# TXn_v1_2_bottomonly.net
KiCad netlist of a schematic drawn in EAGLE
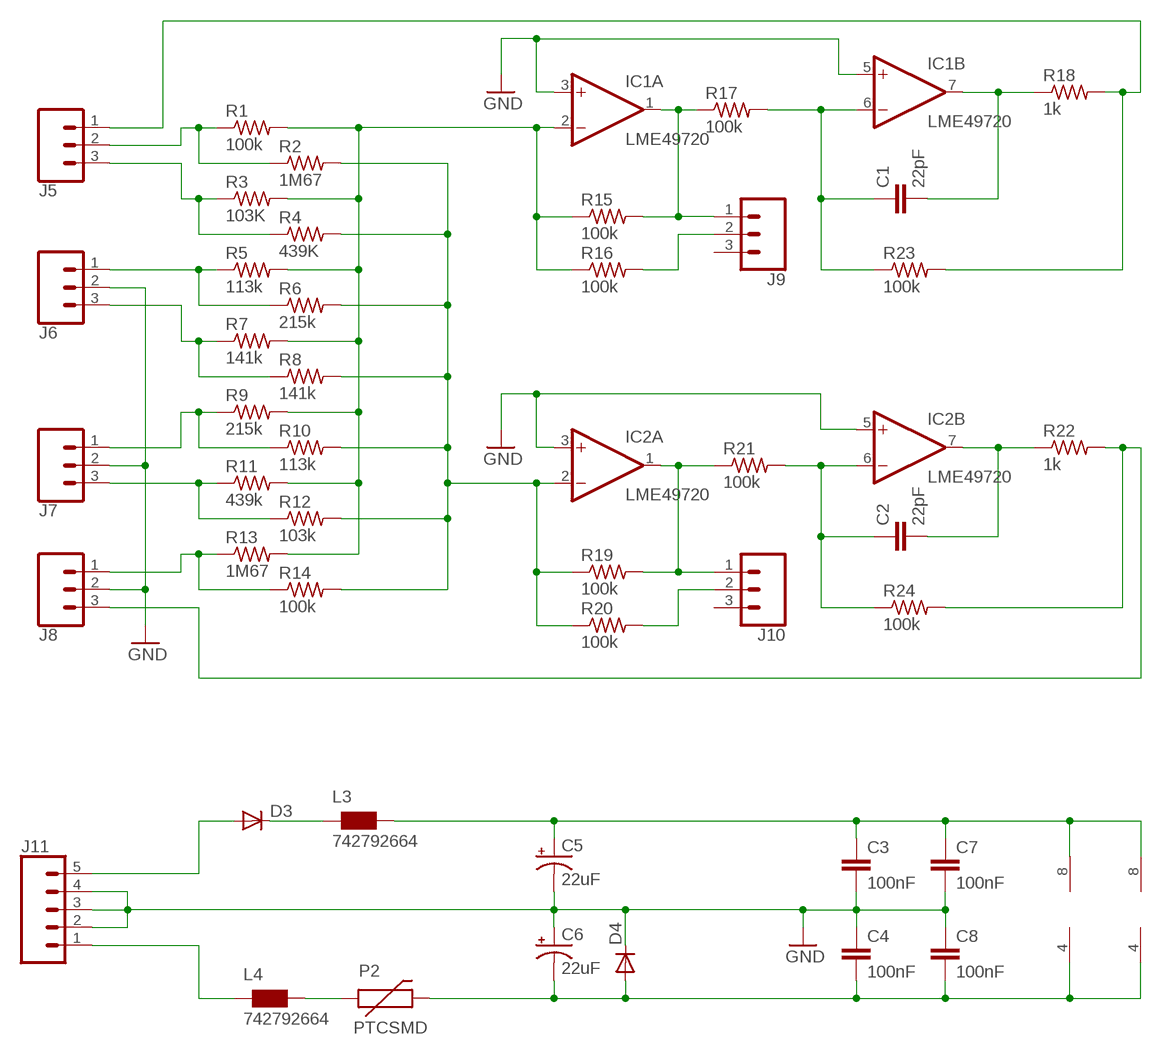
[diagram p0: schematic, sheet 1]

(export (version "E")
  (design (tool "Eeschema 10.0.6"))
  (components
    (comp (ref "C1")
      (value "22pF")
      (footprint "eagle-import:0603-CAP")
      (libsource (lib "eagle-import") (part "CAP0603-CAP"))
    )
    (comp (ref "C2")
      (value "22pF")
      (footprint "eagle-import:0603-CAP")
      (libsource (lib "eagle-import") (part "CAP0603-CAP"))
    )
    (comp (ref "C3")
      (value "100nF")
      (footprint "eagle-import:0603-CAP")
      (libsource (lib "eagle-import") (part "CAP0603-CAP"))
    )
    (comp (ref "C4")
      (value "100nF")
      (footprint "eagle-import:0603-CAP")
      (libsource (lib "eagle-import") (part "CAP0603-CAP"))
    )
    (comp (ref "C5")
      (value "22uF")
      (footprint "eagle-import:PANASONIC_B")
      (libsource (lib "eagle-import") (part "CPOL-USB"))
    )
    (comp (ref "C6")
      (value "22uF")
      (footprint "eagle-import:PANASONIC_B")
      (libsource (lib "eagle-import") (part "CPOL-USB"))
    )
    (comp (ref "C7")
      (value "100nF")
      (footprint "eagle-import:0603-CAP")
      (libsource (lib "eagle-import") (part "CAP0603-CAP"))
    )
    (comp (ref "C8")
      (value "100nF")
      (footprint "eagle-import:0603-CAP")
      (libsource (lib "eagle-import") (part "CAP0603-CAP"))
    )
    (comp (ref "D3")
      (value "DIODE-SOD123")
      (footprint "eagle-import:SOD123")
      (libsource (lib "eagle-import") (part "DIODE-SOD123"))
    )
    (comp (ref "D4")
      (value "DIODE-SOD123")
      (footprint "eagle-import:SOD123")
      (libsource (lib "eagle-import") (part "DIODE-SOD123"))
    )
    (comp (ref "IC1")
      (value "LME49720")
      (footprint "eagle-import:SO08")
      (fields (field (name "SPICEPREFIX") "J"))
      (libsource (lib "eagle-import") (part "TL072D"))
    )
    (comp (ref "IC2")
      (value "LME49720")
      (footprint "eagle-import:SO08")
      (libsource (lib "eagle-import") (part "TL072D"))
    )
    (comp (ref "J5")
      (value "CONN_031X03_NO_SILK")
      (footprint "eagle-import:1X03_NO_SILK")
      (libsource (lib "eagle-import") (part "CONN_031X03_NO_SILK"))
    )
    (comp (ref "J6")
      (value "CONN_031X03_NO_SILK")
      (footprint "eagle-import:1X03_NO_SILK")
      (libsource (lib "eagle-import") (part "CONN_031X03_NO_SILK"))
    )
    (comp (ref "J7")
      (value "CONN_031X03_NO_SILK")
      (footprint "eagle-import:1X03_NO_SILK")
      (libsource (lib "eagle-import") (part "CONN_031X03_NO_SILK"))
    )
    (comp (ref "J8")
      (value "CONN_031X03_NO_SILK")
      (footprint "eagle-import:1X03_NO_SILK")
      (libsource (lib "eagle-import") (part "CONN_031X03_NO_SILK"))
    )
    (comp (ref "J9")
      (value "CONN_031X03_NO_SILK")
      (footprint "eagle-import:1X03_NO_SILK")
      (libsource (lib "eagle-import") (part "CONN_031X03_NO_SILK"))
    )
    (comp (ref "J10")
      (value "CONN_031X03_NO_SILK")
      (footprint "eagle-import:1X03_NO_SILK")
      (libsource (lib "eagle-import") (part "CONN_031X03_NO_SILK"))
    )
    (comp (ref "J11")
      (value "CONN_05NO_SILK")
      (footprint "eagle-import:1X05_NO_SILK")
      (libsource (lib "eagle-import") (part "CONN_05NO_SILK"))
    )
    (comp (ref "L3")
      (value "742792664")
      (footprint "eagle-import:0603")
      (libsource (lib "eagle-import") (part "WE-CBF_0603"))
    )
    (comp (ref "L4")
      (value "742792664")
      (footprint "eagle-import:0603")
      (libsource (lib "eagle-import") (part "WE-CBF_0603"))
    )
    (comp (ref "P2")
      (value "PTCSMD")
      (footprint "eagle-import:PTC-1206")
      (libsource (lib "eagle-import") (part "PTCSMD"))
    )
    (comp (ref "R1")
      (value "100k")
      (footprint "eagle-import:R0603")
      (libsource (lib "eagle-import") (part "R-US_R0603"))
    )
    (comp (ref "R2")
      (value "1M67")
      (footprint "eagle-import:R0603")
      (libsource (lib "eagle-import") (part "R-US_R0603"))
    )
    (comp (ref "R3")
      (value "103K")
      (footprint "eagle-import:R0603")
      (libsource (lib "eagle-import") (part "R-US_R0603"))
    )
    (comp (ref "R4")
      (value "439K")
      (footprint "eagle-import:R0603")
      (libsource (lib "eagle-import") (part "R-US_R0603"))
    )
    (comp (ref "R5")
      (value "113k")
      (footprint "eagle-import:R0603")
      (libsource (lib "eagle-import") (part "R-US_R0603"))
    )
    (comp (ref "R6")
      (value "215k")
      (footprint "eagle-import:R0603")
      (libsource (lib "eagle-import") (part "R-US_R0603"))
    )
    (comp (ref "R7")
      (value "141k")
      (footprint "eagle-import:R0603")
      (libsource (lib "eagle-import") (part "R-US_R0603"))
    )
    (comp (ref "R8")
      (value "141k")
      (footprint "eagle-import:R0603")
      (libsource (lib "eagle-import") (part "R-US_R0603"))
    )
    (comp (ref "R9")
      (value "215k")
      (footprint "eagle-import:R0603")
      (libsource (lib "eagle-import") (part "R-US_R0603"))
    )
    (comp (ref "R10")
      (value "113k")
      (footprint "eagle-import:R0603")
      (libsource (lib "eagle-import") (part "R-US_R0603"))
    )
    (comp (ref "R11")
      (value "439k")
      (footprint "eagle-import:R0603")
      (libsource (lib "eagle-import") (part "R-US_R0603"))
    )
    (comp (ref "R12")
      (value "103k")
      (footprint "eagle-import:R0603")
      (libsource (lib "eagle-import") (part "R-US_R0603"))
    )
    (comp (ref "R13")
      (value "1M67")
      (footprint "eagle-import:R0603")
      (libsource (lib "eagle-import") (part "R-US_R0603"))
    )
    (comp (ref "R14")
      (value "100k")
      (footprint "eagle-import:R0603")
      (libsource (lib "eagle-import") (part "R-US_R0603"))
    )
    (comp (ref "R15")
      (value "100k")
      (footprint "eagle-import:R0603")
      (libsource (lib "eagle-import") (part "R-US_R0603"))
    )
    (comp (ref "R16")
      (value "100k")
      (footprint "eagle-import:R0603")
      (libsource (lib "eagle-import") (part "R-US_R0603"))
    )
    (comp (ref "R17")
      (value "100k")
      (footprint "eagle-import:R0603")
      (libsource (lib "eagle-import") (part "R-US_R0603"))
    )
    (comp (ref "R18")
      (value "1k")
      (footprint "eagle-import:R0603")
      (libsource (lib "eagle-import") (part "R-US_R0603"))
    )
    (comp (ref "R19")
      (value "100k")
      (footprint "eagle-import:R0603")
      (libsource (lib "eagle-import") (part "R-US_R0603"))
    )
    (comp (ref "R20")
      (value "100k")
      (footprint "eagle-import:R0603")
      (libsource (lib "eagle-import") (part "R-US_R0603"))
    )
    (comp (ref "R21")
      (value "100k")
      (footprint "eagle-import:R0603")
      (libsource (lib "eagle-import") (part "R-US_R0603"))
    )
    (comp (ref "R22")
      (value "1k")
      (footprint "eagle-import:R0603")
      (libsource (lib "eagle-import") (part "R-US_R0603"))
    )
    (comp (ref "R23")
      (value "100k")
      (footprint "eagle-import:R0603")
      (libsource (lib "eagle-import") (part "R-US_R0603"))
    )
    (comp (ref "R24")
      (value "100k")
      (footprint "eagle-import:R0603")
      (libsource (lib "eagle-import") (part "R-US_R0603"))
    )
  )
  (nets
    (net (code "1") (name "GND") (class "Default")
      (node (ref "C3") (pin "2") (pinfunction "2_2") (pintype "passive"))
      (node (ref "C4") (pin "1") (pinfunction "1_1") (pintype "passive"))
      (node (ref "C5") (pin "-") (pinfunction "-_-") (pintype "passive"))
      (node (ref "C6") (pin "+") (pinfunction "+_+") (pintype "passive"))
      (node (ref "C7") (pin "2") (pinfunction "2_2") (pintype "passive"))
      (node (ref "C8") (pin "1") (pinfunction "1_1") (pintype "passive"))
      (node (ref "D4") (pin "C") (pinfunction "C_C") (pintype "passive"))
      (node (ref "IC1") (pin "3") (pinfunction "+IN_3") (pintype "input"))
      (node (ref "IC1") (pin "5") (pinfunction "+IN_5") (pintype "input"))
      (node (ref "IC2") (pin "3") (pinfunction "+IN_3") (pintype "input"))
      (node (ref "IC2") (pin "5") (pinfunction "+IN_5") (pintype "input"))
      (node (ref "J11") (pin "2") (pinfunction "2_2") (pintype "passive"))
      (node (ref "J11") (pin "3") (pinfunction "3_3") (pintype "passive"))
      (node (ref "J11") (pin "4") (pinfunction "4_4") (pintype "passive"))
      (node (ref "J6") (pin "2") (pinfunction "2_2") (pintype "passive"))
      (node (ref "J7") (pin "2") (pinfunction "2_2") (pintype "passive"))
      (node (ref "J8") (pin "2") (pinfunction "2_2") (pintype "passive"))
    )
    (net (code "2") (name "Net-(D3-PadA)") (class "Default")
      (node (ref "D3") (pin "A") (pinfunction "A_A") (pintype "passive"))
      (node (ref "J11") (pin "5") (pinfunction "5_5") (pintype "passive"))
    )
    (net (code "3") (name "Net-(D3-PadC)") (class "Default")
      (node (ref "D3") (pin "C") (pinfunction "C_C") (pintype "passive"))
      (node (ref "L3") (pin "1") (pinfunction "1_1") (pintype "passive"))
    )
    (net (code "4") (name "Net-(IC1A--IN)") (class "Default")
      (node (ref "IC1") (pin "2") (pinfunction "-IN_2") (pintype "input"))
      (node (ref "R1") (pin "2") (pinfunction "2_2") (pintype "passive"))
      (node (ref "R11") (pin "2") (pinfunction "2_2") (pintype "passive"))
      (node (ref "R13") (pin "2") (pinfunction "2_2") (pintype "passive"))
      (node (ref "R15") (pin "1") (pinfunction "1_1") (pintype "passive"))
      (node (ref "R16") (pin "1") (pinfunction "1_1") (pintype "passive"))
      (node (ref "R3") (pin "2") (pinfunction "2_2") (pintype "passive"))
      (node (ref "R5") (pin "2") (pinfunction "2_2") (pintype "passive"))
      (node (ref "R7") (pin "2") (pinfunction "2_2") (pintype "passive"))
      (node (ref "R9") (pin "2") (pinfunction "2_2") (pintype "passive"))
    )
    (net (code "5") (name "Net-(IC1A-OUT)") (class "Default")
      (node (ref "IC1") (pin "1") (pinfunction "OUT_1") (pintype "output"))
      (node (ref "J9") (pin "1") (pinfunction "1_1") (pintype "passive"))
      (node (ref "R15") (pin "2") (pinfunction "2_2") (pintype "passive"))
      (node (ref "R17") (pin "1") (pinfunction "1_1") (pintype "passive"))
    )
    (net (code "6") (name "Net-(IC1B--IN)") (class "Default")
      (node (ref "C1") (pin "1") (pinfunction "1_1") (pintype "passive"))
      (node (ref "IC1") (pin "6") (pinfunction "-IN_6") (pintype "input"))
      (node (ref "R17") (pin "2") (pinfunction "2_2") (pintype "passive"))
      (node (ref "R23") (pin "1") (pinfunction "1_1") (pintype "passive"))
    )
    (net (code "7") (name "Net-(IC1B-OUT)") (class "Default")
      (node (ref "C1") (pin "2") (pinfunction "2_2") (pintype "passive"))
      (node (ref "IC1") (pin "7") (pinfunction "OUT_7") (pintype "output"))
      (node (ref "R18") (pin "1") (pinfunction "1_1") (pintype "passive"))
    )
    (net (code "8") (name "Net-(IC1C-V+)") (class "Default")
      (node (ref "C3") (pin "1") (pinfunction "1_1") (pintype "passive"))
      (node (ref "C5") (pin "+") (pinfunction "+_+") (pintype "passive"))
      (node (ref "C7") (pin "1") (pinfunction "1_1") (pintype "passive"))
      (node (ref "IC1") (pin "8") (pinfunction "V+_8") (pintype "power_in"))
      (node (ref "IC2") (pin "8") (pinfunction "V+_8") (pintype "power_in"))
      (node (ref "L3") (pin "2") (pinfunction "2_2") (pintype "passive"))
    )
    (net (code "9") (name "Net-(IC1C-V-)") (class "Default")
      (node (ref "C4") (pin "2") (pinfunction "2_2") (pintype "passive"))
      (node (ref "C6") (pin "-") (pinfunction "-_-") (pintype "passive"))
      (node (ref "C8") (pin "2") (pinfunction "2_2") (pintype "passive"))
      (node (ref "D4") (pin "A") (pinfunction "A_A") (pintype "passive"))
      (node (ref "IC1") (pin "4") (pinfunction "V-_4") (pintype "power_in"))
      (node (ref "IC2") (pin "4") (pinfunction "V-_4") (pintype "power_in"))
      (node (ref "P2") (pin "2") (pinfunction "2_2") (pintype "bidirectional"))
    )
    (net (code "10") (name "Net-(IC2A--IN)") (class "Default")
      (node (ref "IC2") (pin "2") (pinfunction "-IN_2") (pintype "input"))
      (node (ref "R10") (pin "2") (pinfunction "2_2") (pintype "passive"))
      (node (ref "R12") (pin "2") (pinfunction "2_2") (pintype "passive"))
      (node (ref "R14") (pin "2") (pinfunction "2_2") (pintype "passive"))
      (node (ref "R19") (pin "1") (pinfunction "1_1") (pintype "passive"))
      (node (ref "R2") (pin "2") (pinfunction "2_2") (pintype "passive"))
      (node (ref "R20") (pin "1") (pinfunction "1_1") (pintype "passive"))
      (node (ref "R4") (pin "2") (pinfunction "2_2") (pintype "passive"))
      (node (ref "R6") (pin "2") (pinfunction "2_2") (pintype "passive"))
      (node (ref "R8") (pin "2") (pinfunction "2_2") (pintype "passive"))
    )
    (net (code "11") (name "Net-(IC2A-OUT)") (class "Default")
      (node (ref "IC2") (pin "1") (pinfunction "OUT_1") (pintype "output"))
      (node (ref "J10") (pin "1") (pinfunction "1_1") (pintype "passive"))
      (node (ref "R19") (pin "2") (pinfunction "2_2") (pintype "passive"))
      (node (ref "R21") (pin "1") (pinfunction "1_1") (pintype "passive"))
    )
    (net (code "12") (name "Net-(IC2B--IN)") (class "Default")
      (node (ref "C2") (pin "1") (pinfunction "1_1") (pintype "passive"))
      (node (ref "IC2") (pin "6") (pinfunction "-IN_6") (pintype "input"))
      (node (ref "R21") (pin "2") (pinfunction "2_2") (pintype "passive"))
      (node (ref "R24") (pin "1") (pinfunction "1_1") (pintype "passive"))
    )
    (net (code "13") (name "Net-(IC2B-OUT)") (class "Default")
      (node (ref "C2") (pin "2") (pinfunction "2_2") (pintype "passive"))
      (node (ref "IC2") (pin "7") (pinfunction "OUT_7") (pintype "output"))
      (node (ref "R22") (pin "1") (pinfunction "1_1") (pintype "passive"))
    )
    (net (code "14") (name "Net-(J5-Pad1)") (class "Default")
      (node (ref "J5") (pin "1") (pinfunction "1_1") (pintype "passive"))
      (node (ref "R18") (pin "2") (pinfunction "2_2") (pintype "passive"))
      (node (ref "R23") (pin "2") (pinfunction "2_2") (pintype "passive"))
    )
    (net (code "15") (name "Net-(J5-Pad2)") (class "Default")
      (node (ref "J5") (pin "2") (pinfunction "2_2") (pintype "passive"))
      (node (ref "R1") (pin "1") (pinfunction "1_1") (pintype "passive"))
      (node (ref "R2") (pin "1") (pinfunction "1_1") (pintype "passive"))
    )
    (net (code "16") (name "Net-(J5-Pad3)") (class "Default")
      (node (ref "J5") (pin "3") (pinfunction "3_3") (pintype "passive"))
      (node (ref "R3") (pin "1") (pinfunction "1_1") (pintype "passive"))
      (node (ref "R4") (pin "1") (pinfunction "1_1") (pintype "passive"))
    )
    (net (code "17") (name "Net-(J6-Pad1)") (class "Default")
      (node (ref "J6") (pin "1") (pinfunction "1_1") (pintype "passive"))
      (node (ref "R5") (pin "1") (pinfunction "1_1") (pintype "passive"))
      (node (ref "R6") (pin "1") (pinfunction "1_1") (pintype "passive"))
    )
    (net (code "18") (name "Net-(J6-Pad3)") (class "Default")
      (node (ref "J6") (pin "3") (pinfunction "3_3") (pintype "passive"))
      (node (ref "R7") (pin "1") (pinfunction "1_1") (pintype "passive"))
      (node (ref "R8") (pin "1") (pinfunction "1_1") (pintype "passive"))
    )
    (net (code "19") (name "Net-(J7-Pad1)") (class "Default")
      (node (ref "J7") (pin "1") (pinfunction "1_1") (pintype "passive"))
      (node (ref "R10") (pin "1") (pinfunction "1_1") (pintype "passive"))
      (node (ref "R9") (pin "1") (pinfunction "1_1") (pintype "passive"))
    )
    (net (code "20") (name "Net-(J7-Pad3)") (class "Default")
      (node (ref "J7") (pin "3") (pinfunction "3_3") (pintype "passive"))
      (node (ref "R11") (pin "1") (pinfunction "1_1") (pintype "passive"))
      (node (ref "R12") (pin "1") (pinfunction "1_1") (pintype "passive"))
    )
    (net (code "21") (name "Net-(J8-Pad1)") (class "Default")
      (node (ref "J8") (pin "1") (pinfunction "1_1") (pintype "passive"))
      (node (ref "R13") (pin "1") (pinfunction "1_1") (pintype "passive"))
      (node (ref "R14") (pin "1") (pinfunction "1_1") (pintype "passive"))
    )
    (net (code "22") (name "Net-(J8-Pad3)") (class "Default")
      (node (ref "J8") (pin "3") (pinfunction "3_3") (pintype "passive"))
      (node (ref "R22") (pin "2") (pinfunction "2_2") (pintype "passive"))
      (node (ref "R24") (pin "2") (pinfunction "2_2") (pintype "passive"))
    )
    (net (code "23") (name "Net-(J9-Pad2)") (class "Default")
      (node (ref "J9") (pin "2") (pinfunction "2_2") (pintype "passive"))
      (node (ref "R16") (pin "2") (pinfunction "2_2") (pintype "passive"))
    )
    (net (code "24") (name "Net-(J10-Pad2)") (class "Default")
      (node (ref "J10") (pin "2") (pinfunction "2_2") (pintype "passive"))
      (node (ref "R20") (pin "2") (pinfunction "2_2") (pintype "passive"))
    )
    (net (code "25") (name "Net-(J11-Pad1)") (class "Default")
      (node (ref "J11") (pin "1") (pinfunction "1_1") (pintype "passive"))
      (node (ref "L4") (pin "1") (pinfunction "1_1") (pintype "passive"))
    )
    (net (code "26") (name "Net-(L4-Pad2)") (class "Default")
      (node (ref "L4") (pin "2") (pinfunction "2_2") (pintype "passive"))
      (node (ref "P2") (pin "1") (pinfunction "1_1") (pintype "bidirectional"))
    )
    (net (code "27") (name "unconnected-(J9-Pad3)") (class "Default")
      (node (ref "J9") (pin "3") (pinfunction "3_3") (pintype "passive"))
    )
    (net (code "28") (name "unconnected-(J10-Pad3)") (class "Default")
      (node (ref "J10") (pin "3") (pinfunction "3_3") (pintype "passive"))
    )
  )
)
